# as14120_x31_adc.net
KiCad netlist of a schematic drawn in Altium Designer
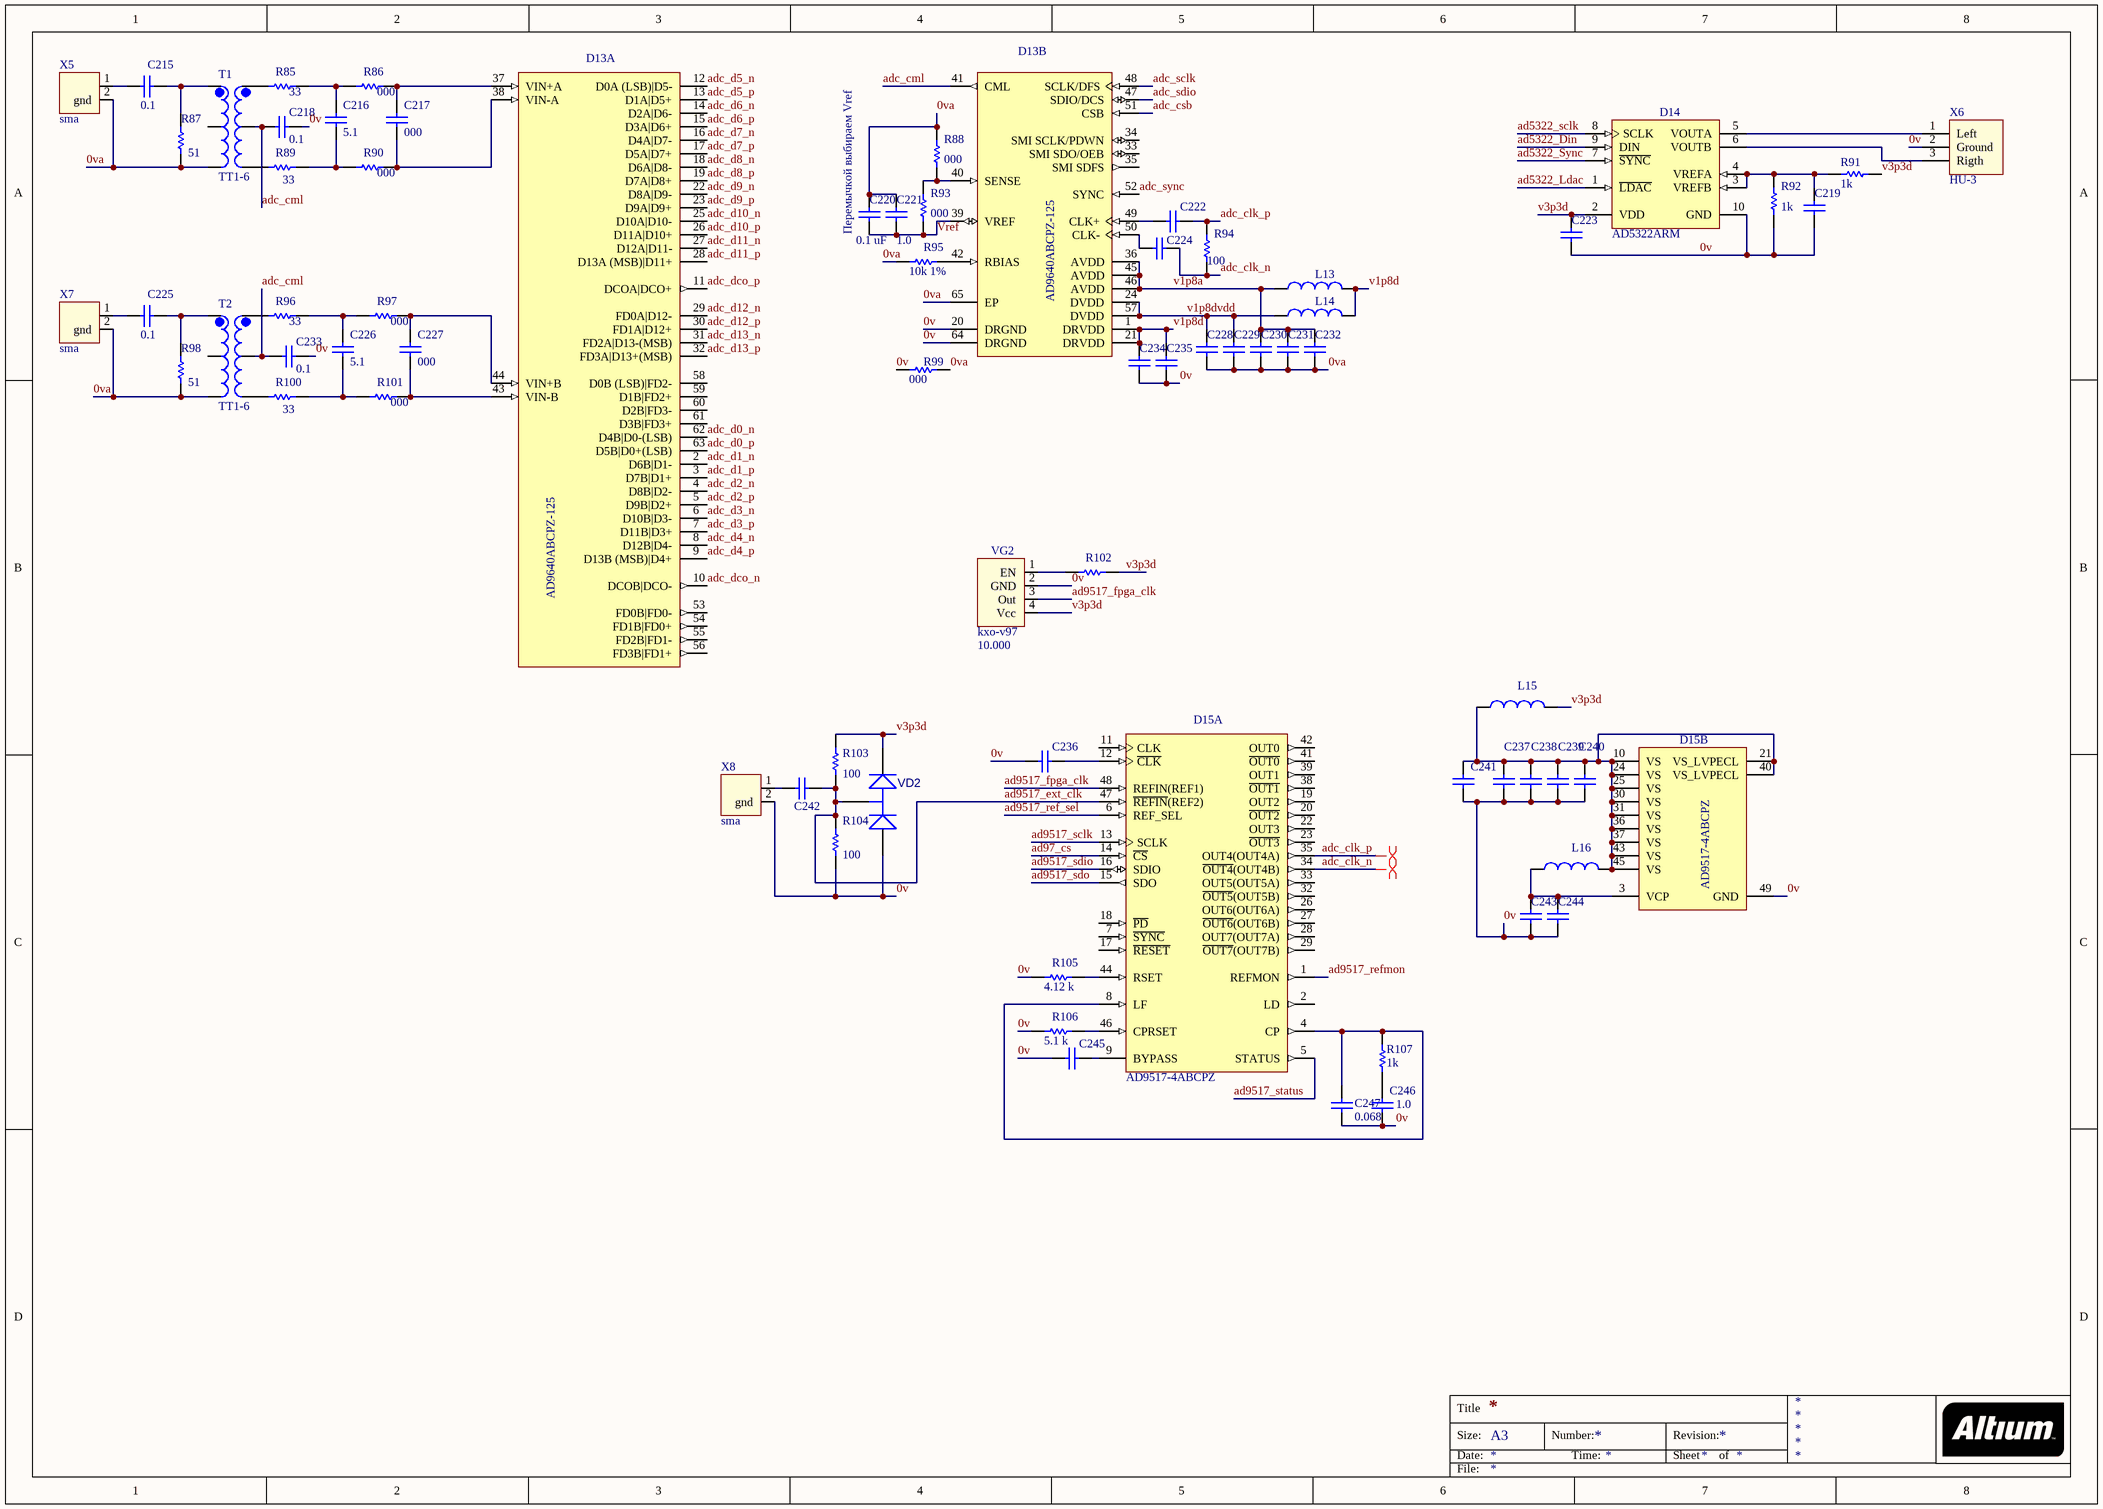
[diagram p0: as14120_x31_adc.SchDoc]

(export (version "E")
  (design (tool "Eeschema 10.0.6"))
  (components
    (comp (ref "C215")
      (value "0.1")
      (footprint "CAPC0402(1005)60_M")
      (description "CAP 1uF 10V ±20% 0402 (1005 Metric) Thickness 0.6mm SMD")
      (fields (field (name "TOLERANCE") "±20%") (field (name "Comment") "CAP 1uF 10V 0402(1005)"))
      (libsource (lib "as14120") (part "CAP_0402"))
    )
    (comp (ref "C216")
      (value "5.1")
      (footprint "CAPC0805(2012)100_N")
      (fields (field (name "Comment") "CAP_0805"))
      (libsource (lib "as14120") (part "CAP_0805"))
    )
    (comp (ref "C217")
      (value "000")
      (footprint "CAPC0805(2012)100_N")
      (fields (field (name "Comment") "CAP_0805"))
      (libsource (lib "as14120") (part "CAP_0805"))
    )
    (comp (ref "C218")
      (value "0.1")
      (footprint "CAPC0402(1005)60_M")
      (description "CAP 1uF 10V ±20% 0402 (1005 Metric) Thickness 0.6mm SMD")
      (fields (field (name "TOLERANCE") "±20%") (field (name "Comment") "CAP 1uF 10V 0402(1005)"))
      (libsource (lib "as14120") (part "CAP_0402"))
    )
    (comp (ref "C219")
      (value "CAP 1uF 10V 0402(1005)")
      (footprint "CAPC0402(1005)60_M")
      (description "CAP 1uF 10V ±20% 0402 (1005 Metric) Thickness 0.6mm SMD")
      (fields (field (name "TOLERANCE") "±20%"))
      (libsource (lib "as14120") (part "CAP_0402"))
    )
    (comp (ref "C220")
      (value "0.1 uF")
      (footprint "CAPC0402(1005)60_M")
      (description "CAP 1uF 10V ±20% 0402 (1005 Metric) Thickness 0.6mm SMD")
      (fields (field (name "TOLERANCE") "±20%") (field (name "Comment") "CAP 1uF 10V 0402(1005)"))
      (libsource (lib "as14120") (part "CAP_0402"))
    )
    (comp (ref "C221")
      (value "1.0")
      (footprint "CAPC0402(1005)60_M")
      (description "CAP 1uF 10V ±20% 0402 (1005 Metric) Thickness 0.6mm SMD")
      (fields (field (name "TOLERANCE") "±20%") (field (name "Comment") "CAP 1uF 10V 0402(1005)"))
      (libsource (lib "as14120") (part "CAP_0402"))
    )
    (comp (ref "C222")
      (value "CAP 1uF 10V 0402(1005)")
      (footprint "CAPC0402(1005)60_M")
      (description "CAP 1uF 10V ±20% 0402 (1005 Metric) Thickness 0.6mm SMD")
      (fields (field (name "TOLERANCE") "±20%"))
      (libsource (lib "as14120") (part "CAP_0402"))
    )
    (comp (ref "C223")
      (value "CAP 1uF 10V 0402(1005)")
      (footprint "CAPC0402(1005)60_M")
      (description "CAP 1uF 10V ±20% 0402 (1005 Metric) Thickness 0.6mm SMD")
      (fields (field (name "TOLERANCE") "±20%"))
      (libsource (lib "as14120") (part "CAP_0402"))
    )
    (comp (ref "C224")
      (value "CAP 1uF 10V 0402(1005)")
      (footprint "CAPC0402(1005)60_M")
      (description "CAP 1uF 10V ±20% 0402 (1005 Metric) Thickness 0.6mm SMD")
      (fields (field (name "TOLERANCE") "±20%"))
      (libsource (lib "as14120") (part "CAP_0402"))
    )
    (comp (ref "C225")
      (value "0.1")
      (footprint "CAPC0402(1005)60_M")
      (description "CAP 1uF 10V ±20% 0402 (1005 Metric) Thickness 0.6mm SMD")
      (fields (field (name "TOLERANCE") "±20%") (field (name "Comment") "CAP 1uF 10V 0402(1005)"))
      (libsource (lib "as14120") (part "CAP_0402"))
    )
    (comp (ref "C226")
      (value "5.1")
      (footprint "CAPC0805(2012)100_N")
      (fields (field (name "Comment") "CAP_0805"))
      (libsource (lib "as14120") (part "CAP_0805"))
    )
    (comp (ref "C227")
      (value "000")
      (footprint "CAPC0805(2012)100_N")
      (fields (field (name "Comment") "CAP_0805"))
      (libsource (lib "as14120") (part "CAP_0805"))
    )
    (comp (ref "C228")
      (value "CAP 1uF 10V 0402(1005)")
      (footprint "CAPC0402(1005)60_M")
      (description "CAP 1uF 10V ±20% 0402 (1005 Metric) Thickness 0.6mm SMD")
      (fields (field (name "TOLERANCE") "±20%"))
      (libsource (lib "as14120") (part "CAP_0402"))
    )
    (comp (ref "C229")
      (value "CAP 1uF 10V 0402(1005)")
      (footprint "CAPC0402(1005)60_M")
      (description "CAP 1uF 10V ±20% 0402 (1005 Metric) Thickness 0.6mm SMD")
      (fields (field (name "TOLERANCE") "±20%"))
      (libsource (lib "as14120") (part "CAP_0402"))
    )
    (comp (ref "C230")
      (value "CAP 1uF 10V 0402(1005)")
      (footprint "CAPC0402(1005)60_M")
      (description "CAP 1uF 10V ±20% 0402 (1005 Metric) Thickness 0.6mm SMD")
      (fields (field (name "TOLERANCE") "±20%"))
      (libsource (lib "as14120") (part "CAP_0402"))
    )
    (comp (ref "C231")
      (value "CAP 1uF 10V 0402(1005)")
      (footprint "CAPC0402(1005)60_M")
      (description "CAP 1uF 10V ±20% 0402 (1005 Metric) Thickness 0.6mm SMD")
      (fields (field (name "TOLERANCE") "±20%"))
      (libsource (lib "as14120") (part "CAP_0402"))
    )
    (comp (ref "C232")
      (value "CAP 1uF 10V 0402(1005)")
      (footprint "CAPC0402(1005)60_M")
      (description "CAP 1uF 10V ±20% 0402 (1005 Metric) Thickness 0.6mm SMD")
      (fields (field (name "TOLERANCE") "±20%"))
      (libsource (lib "as14120") (part "CAP_0402"))
    )
    (comp (ref "C233")
      (value "0.1")
      (footprint "CAPC0402(1005)60_M")
      (description "CAP 1uF 10V ±20% 0402 (1005 Metric) Thickness 0.6mm SMD")
      (fields (field (name "TOLERANCE") "±20%") (field (name "Comment") "CAP 1uF 10V 0402(1005)"))
      (libsource (lib "as14120") (part "CAP_0402"))
    )
    (comp (ref "C234")
      (value "CAP 1uF 10V 0402(1005)")
      (footprint "CAPC0402(1005)60_M")
      (description "CAP 1uF 10V ±20% 0402 (1005 Metric) Thickness 0.6mm SMD")
      (fields (field (name "TOLERANCE") "±20%"))
      (libsource (lib "as14120") (part "CAP_0402"))
    )
    (comp (ref "C235")
      (value "CAP 1uF 10V 0402(1005)")
      (footprint "CAPC0402(1005)60_M")
      (description "CAP 1uF 10V ±20% 0402 (1005 Metric) Thickness 0.6mm SMD")
      (fields (field (name "TOLERANCE") "±20%"))
      (libsource (lib "as14120") (part "CAP_0402"))
    )
    (comp (ref "C236")
      (value "CAP 1uF 10V 0402(1005)")
      (footprint "CAPC0402(1005)60_M")
      (description "CAP 1uF 10V ±20% 0402 (1005 Metric) Thickness 0.6mm SMD")
      (fields (field (name "TOLERANCE") "±20%"))
      (libsource (lib "as14120") (part "CAP_0402"))
    )
    (comp (ref "C237")
      (value "CAP 1uF 10V 0402(1005)")
      (footprint "CAPC0402(1005)60_M")
      (description "CAP 1uF 10V ±20% 0402 (1005 Metric) Thickness 0.6mm SMD")
      (fields (field (name "TOLERANCE") "±20%"))
      (libsource (lib "as14120") (part "CAP_0402"))
    )
    (comp (ref "C238")
      (value "CAP 1uF 10V 0402(1005)")
      (footprint "CAPC0402(1005)60_M")
      (description "CAP 1uF 10V ±20% 0402 (1005 Metric) Thickness 0.6mm SMD")
      (fields (field (name "TOLERANCE") "±20%"))
      (libsource (lib "as14120") (part "CAP_0402"))
    )
    (comp (ref "C239")
      (value "CAP 1uF 10V 0402(1005)")
      (footprint "CAPC0402(1005)60_M")
      (description "CAP 1uF 10V ±20% 0402 (1005 Metric) Thickness 0.6mm SMD")
      (fields (field (name "TOLERANCE") "±20%"))
      (libsource (lib "as14120") (part "CAP_0402"))
    )
    (comp (ref "C240")
      (value "CAP 1uF 10V 0402(1005)")
      (footprint "CAPC0402(1005)60_M")
      (description "CAP 1uF 10V ±20% 0402 (1005 Metric) Thickness 0.6mm SMD")
      (fields (field (name "TOLERANCE") "±20%"))
      (libsource (lib "as14120") (part "CAP_0402"))
    )
    (comp (ref "C241")
      (value "CAP 1uF 10V 0402(1005)")
      (footprint "CAPC0402(1005)60_M")
      (description "CAP 1uF 10V ±20% 0402 (1005 Metric) Thickness 0.6mm SMD")
      (fields (field (name "TOLERANCE") "±20%"))
      (libsource (lib "as14120") (part "CAP_0402"))
    )
    (comp (ref "C242")
      (value "CAP 1uF 10V 0402(1005)")
      (footprint "CAPC0402(1005)60_M")
      (description "CAP 1uF 10V ±20% 0402 (1005 Metric) Thickness 0.6mm SMD")
      (fields (field (name "TOLERANCE") "±20%"))
      (libsource (lib "as14120") (part "CAP_0402"))
    )
    (comp (ref "C243")
      (value "CAP 1uF 10V 0402(1005)")
      (footprint "CAPC0402(1005)60_M")
      (description "CAP 1uF 10V ±20% 0402 (1005 Metric) Thickness 0.6mm SMD")
      (fields (field (name "TOLERANCE") "±20%"))
      (libsource (lib "as14120") (part "CAP_0402"))
    )
    (comp (ref "C244")
      (value "CAP 1uF 10V 0402(1005)")
      (footprint "CAPC0402(1005)60_M")
      (description "CAP 1uF 10V ±20% 0402 (1005 Metric) Thickness 0.6mm SMD")
      (fields (field (name "TOLERANCE") "±20%"))
      (libsource (lib "as14120") (part "CAP_0402"))
    )
    (comp (ref "C245")
      (value "CAP 1uF 10V 0402(1005)")
      (footprint "CAPC0402(1005)60_M")
      (description "CAP 1uF 10V ±20% 0402 (1005 Metric) Thickness 0.6mm SMD")
      (fields (field (name "TOLERANCE") "±20%"))
      (libsource (lib "as14120") (part "CAP_0402"))
    )
    (comp (ref "C246")
      (value "1.0")
      (footprint "CAPC0805(2012)100_N")
      (fields (field (name "Comment") "CAP_0805"))
      (libsource (lib "as14120") (part "CAP_0805"))
    )
    (comp (ref "C247")
      (value "0.068")
      (footprint "CAPC0805(2012)100_N")
      (fields (field (name "Comment") "CAP_0805"))
      (libsource (lib "as14120") (part "CAP_0805"))
    )
    (comp (ref "D13")
      (value "AD9640ABCPZ-125")
      (footprint "CP-64-6_N")
      (fields (field (name "PART NUMBER") "AD9640-125") (field (name "MANUFACTURER") "Analog Devices"))
      (libsource (lib "Analog Devices Data Converters Analog-to-Digital Converters") (part "AD9640ABCPZ-125"))
    )
    (comp (ref "D14")
      (value "AD5322ARM")
      (footprint "RM-10_L")
      (fields (field (name "ADI PART NUMBER") "AD5322") (field (name "MANUFACTURER") "Analog Devices"))
      (libsource (lib "Analog Devices Data Converters Digital-to-Analog Converters") (part "AD5322ARM"))
    )
    (comp (ref "D15")
      (value "AD9517-4ABCPZ")
      (footprint "ADI-CP-48-8_L")
      (libsource (lib "Analog Devices RF IF Timing ICs and Clocks") (part "AD9517-4ABCPZ"))
    )
    (comp (ref "L13")
      (value "BLM21PG300SN1D")
      (footprint "CAPC0805(2012)100_N")
      (libsource (lib "as14120") (part "Ferrite_beat"))
    )
    (comp (ref "L14")
      (value "BLM21PG300SN1D")
      (footprint "CAPC0805(2012)100_N")
      (libsource (lib "as14120") (part "Ferrite_beat"))
    )
    (comp (ref "L15")
      (value "BLM21PG300SN1D")
      (footprint "CAPC0805(2012)100_N")
      (libsource (lib "as14120") (part "Ferrite_beat"))
    )
    (comp (ref "L16")
      (value "BLM21PG300SN1D")
      (footprint "CAPC0805(2012)100_N")
      (libsource (lib "as14120") (part "Ferrite_beat"))
    )
    (comp (ref "R85")
      (value "33")
      (footprint "RESC0805(2012)_L")
      (description "1K 0.125W 1% 0805 (2012 Metric)  SMD")
      (fields (field (name "TOLERANCE") "1 %") (field (name "POWER") "0.125 W"))
      (libsource (lib "as14120") (part "RES_0805"))
    )
    (comp (ref "R86")
      (value "000")
      (footprint "RESC0805(2012)_L")
      (description "1K 0.125W 1% 0805 (2012 Metric)  SMD")
      (fields (field (name "TOLERANCE") "1 %") (field (name "POWER") "0.125 W"))
      (libsource (lib "as14120") (part "RES_0805"))
    )
    (comp (ref "R87")
      (value "51")
      (footprint "RESC0805(2012)_L")
      (description "1K 0.125W 1% 0805 (2012 Metric)  SMD")
      (fields (field (name "TOLERANCE") "1 %") (field (name "POWER") "0.125 W"))
      (libsource (lib "as14120") (part "RES_0805"))
    )
    (comp (ref "R88")
      (value "000")
      (footprint "RESC0603(1608)_L")
      (description "1K 0.1W 5% 0603 (1608 Metric)  SMD")
      (fields (field (name "TOLERANCE") "5 %") (field (name "POWER") "0.1 W"))
      (libsource (lib "as14120") (part "RES_0603"))
    )
    (comp (ref "R89")
      (value "33")
      (footprint "RESC0805(2012)_L")
      (description "1K 0.125W 1% 0805 (2012 Metric)  SMD")
      (fields (field (name "TOLERANCE") "1 %") (field (name "POWER") "0.125 W"))
      (libsource (lib "as14120") (part "RES_0805"))
    )
    (comp (ref "R90")
      (value "000")
      (footprint "RESC0805(2012)_L")
      (description "1K 0.125W 1% 0805 (2012 Metric)  SMD")
      (fields (field (name "TOLERANCE") "1 %") (field (name "POWER") "0.125 W"))
      (libsource (lib "as14120") (part "RES_0805"))
    )
    (comp (ref "R91")
      (value "1k")
      (footprint "RESC0603(1608)_L")
      (description "1K 0.1W 5% 0603 (1608 Metric)  SMD")
      (fields (field (name "TOLERANCE") "5 %") (field (name "POWER") "0.1 W"))
      (libsource (lib "as14120") (part "RES_0603"))
    )
    (comp (ref "R92")
      (value "1k")
      (footprint "RESC0603(1608)_L")
      (description "1K 0.1W 5% 0603 (1608 Metric)  SMD")
      (fields (field (name "TOLERANCE") "5 %") (field (name "POWER") "0.1 W"))
      (libsource (lib "as14120") (part "RES_0603"))
    )
    (comp (ref "R93")
      (value "000")
      (footprint "RESC0603(1608)_L")
      (description "1K 0.1W 5% 0603 (1608 Metric)  SMD")
      (fields (field (name "TOLERANCE") "5 %") (field (name "POWER") "0.1 W"))
      (libsource (lib "as14120") (part "RES_0603"))
    )
    (comp (ref "R94")
      (value "100")
      (footprint "RESC0805(2012)_L")
      (description "1K 0.125W 1% 0805 (2012 Metric)  SMD")
      (fields (field (name "TOLERANCE") "1 %") (field (name "POWER") "0.125 W"))
      (libsource (lib "as14120") (part "RES_0805"))
    )
    (comp (ref "R95")
      (value "10k 1%")
      (footprint "RESC0805(2012)_L")
      (description "1K 0.125W 1% 0805 (2012 Metric)  SMD")
      (fields (field (name "TOLERANCE") "1 %") (field (name "POWER") "0.125 W"))
      (libsource (lib "as14120") (part "RES_0805"))
    )
    (comp (ref "R96")
      (value "33")
      (footprint "RESC0805(2012)_L")
      (description "1K 0.125W 1% 0805 (2012 Metric)  SMD")
      (fields (field (name "TOLERANCE") "1 %") (field (name "POWER") "0.125 W"))
      (libsource (lib "as14120") (part "RES_0805"))
    )
    (comp (ref "R97")
      (value "000")
      (footprint "RESC0805(2012)_L")
      (description "1K 0.125W 1% 0805 (2012 Metric)  SMD")
      (fields (field (name "TOLERANCE") "1 %") (field (name "POWER") "0.125 W"))
      (libsource (lib "as14120") (part "RES_0805"))
    )
    (comp (ref "R98")
      (value "51")
      (footprint "RESC0805(2012)_L")
      (description "1K 0.125W 1% 0805 (2012 Metric)  SMD")
      (fields (field (name "TOLERANCE") "1 %") (field (name "POWER") "0.125 W"))
      (libsource (lib "as14120") (part "RES_0805"))
    )
    (comp (ref "R99")
      (value "000")
      (footprint "RESC0603(1608)_L")
      (description "1K 0.1W 5% 0603 (1608 Metric)  SMD")
      (fields (field (name "TOLERANCE") "5 %") (field (name "POWER") "0.1 W"))
      (libsource (lib "as14120") (part "RES_0603"))
    )
    (comp (ref "R100")
      (value "33")
      (footprint "RESC0805(2012)_L")
      (description "1K 0.125W 1% 0805 (2012 Metric)  SMD")
      (fields (field (name "TOLERANCE") "1 %") (field (name "POWER") "0.125 W"))
      (libsource (lib "as14120") (part "RES_0805"))
    )
    (comp (ref "R101")
      (value "000")
      (footprint "RESC0805(2012)_L")
      (description "1K 0.125W 1% 0805 (2012 Metric)  SMD")
      (fields (field (name "TOLERANCE") "1 %") (field (name "POWER") "0.125 W"))
      (libsource (lib "as14120") (part "RES_0805"))
    )
    (comp (ref "R102")
      (value "1K 5% 0603(1608)")
      (footprint "RESC0603(1608)_L")
      (description "1K 0.1W 5% 0603 (1608 Metric)  SMD")
      (fields (field (name "TOLERANCE") "5 %") (field (name "POWER") "0.1 W"))
      (libsource (lib "as14120") (part "RES_0603"))
    )
    (comp (ref "R103")
      (value "100")
      (footprint "RESC0805(2012)_L")
      (description "1K 0.125W 1% 0805 (2012 Metric)  SMD")
      (fields (field (name "TOLERANCE") "1 %") (field (name "POWER") "0.125 W"))
      (libsource (lib "as14120") (part "RES_0805"))
    )
    (comp (ref "R104")
      (value "100")
      (footprint "RESC0805(2012)_L")
      (description "1K 0.125W 1% 0805 (2012 Metric)  SMD")
      (fields (field (name "TOLERANCE") "1 %") (field (name "POWER") "0.125 W"))
      (libsource (lib "as14120") (part "RES_0805"))
    )
    (comp (ref "R105")
      (value "4.12 k")
      (footprint "RESC0805(2012)_L")
      (description "1K 0.125W 1% 0805 (2012 Metric)  SMD")
      (fields (field (name "TOLERANCE") "1 %") (field (name "POWER") "0.125 W"))
      (libsource (lib "as14120") (part "RES_0805"))
    )
    (comp (ref "R106")
      (value "5.1 k")
      (footprint "RESC0805(2012)_L")
      (description "1K 0.125W 1% 0805 (2012 Metric)  SMD")
      (fields (field (name "TOLERANCE") "1 %") (field (name "POWER") "0.125 W"))
      (libsource (lib "as14120") (part "RES_0805"))
    )
    (comp (ref "R107")
      (value "1k")
      (footprint "RESC0805(2012)_L")
      (description "1K 0.125W 1% 0805 (2012 Metric)  SMD")
      (fields (field (name "TOLERANCE") "1 %") (field (name "POWER") "0.125 W"))
      (libsource (lib "as14120") (part "RES_0805"))
    )
    (comp (ref "T1") (value "TT1-6") (footprint "TT!-6-KK81") (libsource (lib "as14120") (part "TT1-6-KK81")))
    (comp (ref "T2") (value "TT1-6") (footprint "TT!-6-KK81") (libsource (lib "as14120") (part "TT1-6-KK81")))
    (comp (ref "VD2")
      (value "BAV99")
      (footprint "SO-G3/X.9")
      (description "SOT23 Silicon Planar High-Speed Switching Series Diode Pair")
      (libsource (lib "alexsb") (part "BAV99"))
    )
    (comp (ref "VG2")
      (value "kxo-v97")
      (footprint "kxo-v97")
      (fields (field (name "ALTIUM_VALUE") "10.000"))
      (libsource (lib "as14120") (part "kxo-v97"))
    )
    (comp (ref "X5") (value "sma") (footprint "sma") (libsource (lib "as14120") (part "sma")))
    (comp (ref "X6") (value "HU-3") (footprint "HU-3") (libsource (lib "as14120") (part "HU-3")))
    (comp (ref "X7") (value "sma") (footprint "sma") (libsource (lib "as14120") (part "sma")))
    (comp (ref "X8") (value "sma") (footprint "sma") (libsource (lib "as14120") (part "sma")))
  )
  (nets
    (net (code "1") (name "/0v") (class "Default")
      (node (ref "C218") (pin "2") (pinfunction "2_2") (pintype "passive"))
      (node (ref "C219") (pin "1") (pinfunction "1_1") (pintype "passive"))
      (node (ref "C223") (pin "1") (pinfunction "1_1") (pintype "passive"))
      (node (ref "C233") (pin "2") (pinfunction "2_2") (pintype "passive"))
      (node (ref "C234") (pin "1") (pinfunction "1_1") (pintype "passive"))
      (node (ref "C235") (pin "1") (pinfunction "1_1") (pintype "passive"))
      (node (ref "C236") (pin "1") (pinfunction "1_1") (pintype "passive"))
      (node (ref "C237") (pin "1") (pinfunction "1_1") (pintype "passive"))
      (node (ref "C238") (pin "1") (pinfunction "1_1") (pintype "passive"))
      (node (ref "C239") (pin "1") (pinfunction "1_1") (pintype "passive"))
      (node (ref "C240") (pin "1") (pinfunction "1_1") (pintype "passive"))
      (node (ref "C241") (pin "1") (pinfunction "1_1") (pintype "passive"))
      (node (ref "C243") (pin "1") (pinfunction "1_1") (pintype "passive"))
      (node (ref "C244") (pin "1") (pinfunction "1_1") (pintype "passive"))
      (node (ref "C245") (pin "1") (pinfunction "1_1") (pintype "passive"))
      (node (ref "C246") (pin "1") (pinfunction "1_1") (pintype "passive"))
      (node (ref "C247") (pin "1") (pinfunction "1_1") (pintype "passive"))
      (node (ref "D13") (pin "20") (pinfunction "DRGND_20") (pintype "power_in"))
      (node (ref "D13") (pin "64") (pinfunction "DRGND_64") (pintype "power_in"))
      (node (ref "D14") (pin "10") (pinfunction "GND_10") (pintype "power_in"))
      (node (ref "D15") (pin "49") (pinfunction "GND_49") (pintype "power_in"))
      (node (ref "R104") (pin "1") (pinfunction "1_1") (pintype "passive"))
      (node (ref "R105") (pin "2") (pinfunction "2_2") (pintype "passive"))
      (node (ref "R106") (pin "2") (pinfunction "2_2") (pintype "passive"))
      (node (ref "R92") (pin "2") (pinfunction "2_2") (pintype "passive"))
      (node (ref "R99") (pin "1") (pinfunction "1_1") (pintype "passive"))
      (node (ref "VD2") (pin "3") (pinfunction "A_3") (pintype "passive"))
      (node (ref "VG2") (pin "2") (pinfunction "GND_2") (pintype "passive"))
      (node (ref "X6") (pin "2") (pinfunction "Ground_2") (pintype "passive"))
      (node (ref "X8") (pin "2") (pinfunction "gnd_2") (pintype "passive"))
    )
    (net (code "2") (name "/0va") (class "Default")
      (node (ref "C220") (pin "2") (pinfunction "2_2") (pintype "passive"))
      (node (ref "C221") (pin "2") (pinfunction "2_2") (pintype "passive"))
      (node (ref "C228") (pin "1") (pinfunction "1_1") (pintype "passive"))
      (node (ref "C229") (pin "1") (pinfunction "1_1") (pintype "passive"))
      (node (ref "C230") (pin "1") (pinfunction "1_1") (pintype "passive"))
      (node (ref "C231") (pin "1") (pinfunction "1_1") (pintype "passive"))
      (node (ref "C232") (pin "1") (pinfunction "1_1") (pintype "passive"))
      (node (ref "D13") (pin "65") (pinfunction "EP_65") (pintype "power_in"))
      (node (ref "R87") (pin "1") (pinfunction "1_1") (pintype "passive"))
      (node (ref "R88") (pin "1") (pinfunction "1_1") (pintype "passive"))
      (node (ref "R95") (pin "2") (pinfunction "2_2") (pintype "passive"))
      (node (ref "R98") (pin "1") (pinfunction "1_1") (pintype "passive"))
      (node (ref "R99") (pin "2") (pinfunction "2_2") (pintype "passive"))
      (node (ref "T1") (pin "6") (pinfunction "6_6") (pintype "passive"))
      (node (ref "T2") (pin "6") (pinfunction "6_6") (pintype "passive"))
      (node (ref "X5") (pin "2") (pinfunction "gnd_2") (pintype "passive"))
      (node (ref "X7") (pin "2") (pinfunction "gnd_2") (pintype "passive"))
    )
    (net (code "3") (name "/Vref") (class "Default")
      (node (ref "C220") (pin "1") (pinfunction "1_1") (pintype "passive"))
      (node (ref "C221") (pin "1") (pinfunction "1_1") (pintype "passive"))
      (node (ref "D13") (pin "39") (pinfunction "VREF_39") (pintype "bidirectional"))
      (node (ref "R93") (pin "2") (pinfunction "2_2") (pintype "passive"))
    )
    (net (code "4") (name "/ad97_cs") (class "Default")
      (node (ref "D15") (pin "14") (pinfunction "~{CS}_14") (pintype "input"))
    )
    (net (code "5") (name "/ad5322_Din") (class "Default")
      (node (ref "D14") (pin "9") (pinfunction "DIN_9") (pintype "input"))
    )
    (net (code "6") (name "/ad5322_Ldac") (class "Default")
      (node (ref "D14") (pin "1") (pinfunction "~{LDAC}_1") (pintype "input"))
    )
    (net (code "7") (name "/ad5322_Sync") (class "Default")
      (node (ref "D14") (pin "7") (pinfunction "~{SYNC}_7") (pintype "input"))
    )
    (net (code "8") (name "/ad5322_sclk") (class "Default")
      (node (ref "D14") (pin "8") (pinfunction "SCLK_8") (pintype "input"))
    )
    (net (code "9") (name "/ad9517_ext_clk") (class "Default")
      (node (ref "C242") (pin "2") (pinfunction "2_2") (pintype "passive"))
      (node (ref "D15") (pin "47") (pinfunction "~{REFIN}(REF2)_47") (pintype "input"))
      (node (ref "R103") (pin "1") (pinfunction "1_1") (pintype "passive"))
      (node (ref "R104") (pin "2") (pinfunction "2_2") (pintype "passive"))
      (node (ref "VD2") (pin "1") (pinfunction "C_1") (pintype "passive"))
    )
    (net (code "10") (name "/ad9517_fpga_clk") (class "Default")
      (node (ref "D15") (pin "48") (pinfunction "REFIN(REF1)_48") (pintype "input"))
      (node (ref "VG2") (pin "3") (pinfunction "Out_3") (pintype "passive"))
    )
    (net (code "11") (name "/ad9517_ref_sel") (class "Default")
      (node (ref "D15") (pin "6") (pinfunction "REF_SEL_6") (pintype "input"))
    )
    (net (code "12") (name "/ad9517_refmon") (class "Default")
      (node (ref "D15") (pin "1") (pinfunction "REFMON_1") (pintype "output"))
    )
    (net (code "13") (name "/ad9517_sclk") (class "Default")
      (node (ref "D15") (pin "13") (pinfunction "SCLK_13") (pintype "input"))
    )
    (net (code "14") (name "/ad9517_sdio") (class "Default")
      (node (ref "D15") (pin "16") (pinfunction "SDIO_16") (pintype "bidirectional"))
    )
    (net (code "15") (name "/ad9517_sdo") (class "Default")
      (node (ref "D15") (pin "15") (pinfunction "SDO_15") (pintype "output"))
    )
    (net (code "16") (name "/ad9517_status") (class "Default")
      (node (ref "D15") (pin "5") (pinfunction "STATUS_5") (pintype "output"))
    )
    (net (code "17") (name "/adc_clk_n") (class "Default")
      (node (ref "C224") (pin "1") (pinfunction "1_1") (pintype "passive"))
      (node (ref "D15") (pin "34") (pinfunction "~{OUT4}(OUT4B)_34") (pintype "output"))
      (node (ref "R94") (pin "1") (pinfunction "1_1") (pintype "passive"))
    )
    (net (code "18") (name "/adc_clk_p") (class "Default")
      (node (ref "C222") (pin "1") (pinfunction "1_1") (pintype "passive"))
      (node (ref "D15") (pin "35") (pinfunction "OUT4(OUT4A)_35") (pintype "output"))
      (node (ref "R94") (pin "2") (pinfunction "2_2") (pintype "passive"))
    )
    (net (code "19") (name "/adc_cml") (class "Default")
      (node (ref "C218") (pin "1") (pinfunction "1_1") (pintype "passive"))
      (node (ref "C233") (pin "1") (pinfunction "1_1") (pintype "passive"))
      (node (ref "D13") (pin "41") (pinfunction "CML_41") (pintype "output"))
      (node (ref "T1") (pin "2") (pinfunction "2_2") (pintype "passive"))
      (node (ref "T2") (pin "2") (pinfunction "2_2") (pintype "passive"))
    )
    (net (code "20") (name "/adc_csb") (class "Default")
      (node (ref "D13") (pin "51") (pinfunction "CSB_51") (pintype "input"))
    )
    (net (code "21") (name "/adc_d0_n") (class "Default")
      (node (ref "D13") (pin "62") (pinfunction "D4BD0-(LSB)_62") (pintype "tri_state"))
    )
    (net (code "22") (name "/adc_d0_p") (class "Default")
      (node (ref "D13") (pin "63") (pinfunction "D5BD0+(LSB)_63") (pintype "tri_state"))
    )
    (net (code "23") (name "/adc_d1_n") (class "Default")
      (node (ref "D13") (pin "2") (pinfunction "D6BD1-_2") (pintype "tri_state"))
    )
    (net (code "24") (name "/adc_d1_p") (class "Default")
      (node (ref "D13") (pin "3") (pinfunction "D7BD1+_3") (pintype "tri_state"))
    )
    (net (code "25") (name "/adc_d2_n") (class "Default")
      (node (ref "D13") (pin "4") (pinfunction "D8BD2-_4") (pintype "tri_state"))
    )
    (net (code "26") (name "/adc_d2_p") (class "Default")
      (node (ref "D13") (pin "5") (pinfunction "D9BD2+_5") (pintype "tri_state"))
    )
    (net (code "27") (name "/adc_d3_n") (class "Default")
      (node (ref "D13") (pin "6") (pinfunction "D10BD3-_6") (pintype "tri_state"))
    )
    (net (code "28") (name "/adc_d3_p") (class "Default")
      (node (ref "D13") (pin "7") (pinfunction "D11BD3+_7") (pintype "tri_state"))
    )
    (net (code "29") (name "/adc_d4_n") (class "Default")
      (node (ref "D13") (pin "8") (pinfunction "D12BD4-_8") (pintype "tri_state"))
    )
    (net (code "30") (name "/adc_d4_p") (class "Default")
      (node (ref "D13") (pin "9") (pinfunction "D13B_(MSB)D4+_9") (pintype "tri_state"))
    )
    (net (code "31") (name "/adc_d5_n") (class "Default")
      (node (ref "D13") (pin "12") (pinfunction "D0A_(LSB)D5-_12") (pintype "tri_state"))
    )
    (net (code "32") (name "/adc_d5_p") (class "Default")
      (node (ref "D13") (pin "13") (pinfunction "D1AD5+_13") (pintype "tri_state"))
    )
    (net (code "33") (name "/adc_d6_n") (class "Default")
      (node (ref "D13") (pin "14") (pinfunction "D2AD6-_14") (pintype "tri_state"))
    )
    (net (code "34") (name "/adc_d6_p") (class "Default")
      (node (ref "D13") (pin "15") (pinfunction "D3AD6+_15") (pintype "tri_state"))
    )
    (net (code "35") (name "/adc_d7_n") (class "Default")
      (node (ref "D13") (pin "16") (pinfunction "D4AD7-_16") (pintype "tri_state"))
    )
    (net (code "36") (name "/adc_d7_p") (class "Default")
      (node (ref "D13") (pin "17") (pinfunction "D5AD7+_17") (pintype "tri_state"))
    )
    (net (code "37") (name "/adc_d8_n") (class "Default")
      (node (ref "D13") (pin "18") (pinfunction "D6AD8-_18") (pintype "tri_state"))
    )
    (net (code "38") (name "/adc_d8_p") (class "Default")
      (node (ref "D13") (pin "19") (pinfunction "D7AD8+_19") (pintype "tri_state"))
    )
    (net (code "39") (name "/adc_d9_n") (class "Default")
      (node (ref "D13") (pin "22") (pinfunction "D8AD9-_22") (pintype "tri_state"))
    )
    (net (code "40") (name "/adc_d9_p") (class "Default")
      (node (ref "D13") (pin "23") (pinfunction "D9AD9+_23") (pintype "tri_state"))
    )
    (net (code "41") (name "/adc_d10_n") (class "Default")
      (node (ref "D13") (pin "25") (pinfunction "D10AD10-_25") (pintype "tri_state"))
    )
    (net (code "42") (name "/adc_d10_p") (class "Default")
      (node (ref "D13") (pin "26") (pinfunction "D11AD10+_26") (pintype "tri_state"))
    )
    (net (code "43") (name "/adc_d11_n") (class "Default")
      (node (ref "D13") (pin "27") (pinfunction "D12AD11-_27") (pintype "tri_state"))
    )
    (net (code "44") (name "/adc_d11_p") (class "Default")
      (node (ref "D13") (pin "28") (pinfunction "D13A_(MSB)D11+_28") (pintype "tri_state"))
    )
    (net (code "45") (name "/adc_d12_n") (class "Default")
      (node (ref "D13") (pin "29") (pinfunction "FD0AD12-_29") (pintype "tri_state"))
    )
    (net (code "46") (name "/adc_d12_p") (class "Default")
      (node (ref "D13") (pin "30") (pinfunction "FD1AD12+_30") (pintype "tri_state"))
    )
    (net (code "47") (name "/adc_d13_n") (class "Default")
      (node (ref "D13") (pin "31") (pinfunction "FD2AD13-(MSB)_31") (pintype "tri_state"))
    )
    (net (code "48") (name "/adc_d13_p") (class "Default")
      (node (ref "D13") (pin "32") (pinfunction "FD3AD13+(MSB)_32") (pintype "tri_state"))
    )
    (net (code "49") (name "/adc_dco_n") (class "Default")
      (node (ref "D13") (pin "10") (pinfunction "DCOBDCO-_10") (pintype "output"))
    )
    (net (code "50") (name "/adc_dco_p") (class "Default")
      (node (ref "D13") (pin "11") (pinfunction "DCOADCO+_11") (pintype "output"))
    )
    (net (code "51") (name "/adc_sclk") (class "Default")
      (node (ref "D13") (pin "48") (pinfunction "SCLK/DFS_48") (pintype "input"))
    )
    (net (code "52") (name "/adc_sdio") (class "Default")
      (node (ref "D13") (pin "47") (pinfunction "SDIO/DCS_47") (pintype "bidirectional"))
    )
    (net (code "53") (name "/adc_sync") (class "Default")
      (node (ref "D13") (pin "52") (pinfunction "SYNC_52") (pintype "input"))
    )
    (net (code "54") (name "/v1p8a") (class "Default")
      (node (ref "C230") (pin "2") (pinfunction "2_2") (pintype "passive"))
      (node (ref "C231") (pin "2") (pinfunction "2_2") (pintype "passive"))
      (node (ref "C232") (pin "2") (pinfunction "2_2") (pintype "passive"))
      (node (ref "D13") (pin "36") (pinfunction "AVDD_36") (pintype "power_in"))
      (node (ref "D13") (pin "45") (pinfunction "AVDD_45") (pintype "power_in"))
      (node (ref "D13") (pin "46") (pinfunction "AVDD_46") (pintype "power_in"))
      (node (ref "L13") (pin "1") (pinfunction "1_1") (pintype "passive"))
    )
    (net (code "55") (name "/v1p8d") (class "Default")
      (node (ref "C234") (pin "2") (pinfunction "2_2") (pintype "passive"))
      (node (ref "C235") (pin "2") (pinfunction "2_2") (pintype "passive"))
      (node (ref "D13") (pin "1") (pinfunction "DRVDD_1") (pintype "power_in"))
      (node (ref "D13") (pin "21") (pinfunction "DRVDD_21") (pintype "power_in"))
      (node (ref "L13") (pin "2") (pinfunction "2_2") (pintype "passive"))
      (node (ref "L14") (pin "2") (pinfunction "2_2") (pintype "passive"))
    )
    (net (code "56") (name "/v1p8dvdd") (class "Default")
      (node (ref "C228") (pin "2") (pinfunction "2_2") (pintype "passive"))
      (node (ref "C229") (pin "2") (pinfunction "2_2") (pintype "passive"))
      (node (ref "D13") (pin "24") (pinfunction "DVDD_24") (pintype "power_in"))
      (node (ref "D13") (pin "57") (pinfunction "DVDD_57") (pintype "power_in"))
      (node (ref "L14") (pin "1") (pinfunction "1_1") (pintype "passive"))
    )
    (net (code "57") (name "/v3p3d") (class "Default")
      (node (ref "C223") (pin "2") (pinfunction "2_2") (pintype "passive"))
      (node (ref "D14") (pin "2") (pinfunction "VDD_2") (pintype "power_in"))
      (node (ref "L15") (pin "2") (pinfunction "2_2") (pintype "passive"))
      (node (ref "R102") (pin "1") (pinfunction "1_1") (pintype "passive"))
      (node (ref "R103") (pin "2") (pinfunction "2_2") (pintype "passive"))
      (node (ref "R91") (pin "2") (pinfunction "2_2") (pintype "passive"))
      (node (ref "VD2") (pin "2") (pinfunction "K_2") (pintype "passive"))
      (node (ref "VG2") (pin "4") (pinfunction "Vcc_4") (pintype "passive"))
    )
    (net (code "58") (name "Net-(C215-Pad1)") (class "Default")
      (node (ref "C215") (pin "1") (pinfunction "1_1") (pintype "passive"))
      (node (ref "X5") (pin "1") (pintype "passive"))
    )
    (net (code "59") (name "Net-(C215-Pad2)") (class "Default")
      (node (ref "C215") (pin "2") (pinfunction "2_2") (pintype "passive"))
      (node (ref "R87") (pin "2") (pinfunction "2_2") (pintype "passive"))
      (node (ref "T1") (pin "4") (pinfunction "4_4") (pintype "passive"))
    )
    (net (code "60") (name "Net-(C216-Pad1)") (class "Default")
      (node (ref "C216") (pin "1") (pinfunction "1_1") (pintype "passive"))
      (node (ref "R89") (pin "1") (pinfunction "1_1") (pintype "passive"))
      (node (ref "R90") (pin "2") (pinfunction "2_2") (pintype "passive"))
    )
    (net (code "61") (name "Net-(C216-Pad2)") (class "Default")
      (node (ref "C216") (pin "2") (pinfunction "2_2") (pintype "passive"))
      (node (ref "R85") (pin "1") (pinfunction "1_1") (pintype "passive"))
      (node (ref "R86") (pin "2") (pinfunction "2_2") (pintype "passive"))
    )
    (net (code "62") (name "Net-(C225-Pad1)") (class "Default")
      (node (ref "C225") (pin "1") (pinfunction "1_1") (pintype "passive"))
      (node (ref "X7") (pin "1") (pintype "passive"))
    )
    (net (code "63") (name "Net-(C225-Pad2)") (class "Default")
      (node (ref "C225") (pin "2") (pinfunction "2_2") (pintype "passive"))
      (node (ref "R98") (pin "2") (pinfunction "2_2") (pintype "passive"))
      (node (ref "T2") (pin "4") (pinfunction "4_4") (pintype "passive"))
    )
    (net (code "64") (name "Net-(C226-Pad1)") (class "Default")
      (node (ref "C226") (pin "1") (pinfunction "1_1") (pintype "passive"))
      (node (ref "R100") (pin "1") (pinfunction "1_1") (pintype "passive"))
      (node (ref "R101") (pin "2") (pinfunction "2_2") (pintype "passive"))
    )
    (net (code "65") (name "Net-(C226-Pad2)") (class "Default")
      (node (ref "C226") (pin "2") (pinfunction "2_2") (pintype "passive"))
      (node (ref "R96") (pin "1") (pinfunction "1_1") (pintype "passive"))
      (node (ref "R97") (pin "2") (pinfunction "2_2") (pintype "passive"))
    )
    (net (code "66") (name "Net-(C237-Pad2)") (class "Default")
      (node (ref "C237") (pin "2") (pinfunction "2_2") (pintype "passive"))
      (node (ref "C238") (pin "2") (pinfunction "2_2") (pintype "passive"))
      (node (ref "C239") (pin "2") (pinfunction "2_2") (pintype "passive"))
      (node (ref "C240") (pin "2") (pinfunction "2_2") (pintype "passive"))
      (node (ref "C241") (pin "2") (pinfunction "2_2") (pintype "passive"))
      (node (ref "D15") (pin "10") (pinfunction "VS_10") (pintype "power_in"))
      (node (ref "D15") (pin "21") (pinfunction "VS_LVPECL_21") (pintype "power_in"))
      (node (ref "D15") (pin "24") (pinfunction "VS_24") (pintype "power_in"))
      (node (ref "D15") (pin "25") (pinfunction "VS_25") (pintype "power_in"))
      (node (ref "D15") (pin "30") (pinfunction "VS_30") (pintype "power_in"))
      (node (ref "D15") (pin "31") (pinfunction "VS_31") (pintype "power_in"))
      (node (ref "D15") (pin "36") (pinfunction "VS_36") (pintype "power_in"))
      (node (ref "D15") (pin "37") (pinfunction "VS_37") (pintype "power_in"))
      (node (ref "D15") (pin "40") (pinfunction "VS_LVPECL_40") (pintype "power_in"))
      (node (ref "D15") (pin "43") (pinfunction "VS_43") (pintype "power_in"))
      (node (ref "D15") (pin "45") (pinfunction "VS_45") (pintype "power_in"))
      (node (ref "L15") (pin "1") (pinfunction "1_1") (pintype "passive"))
      (node (ref "L16") (pin "2") (pinfunction "2_2") (pintype "passive"))
    )
    (net (code "67") (name "Net-(C242-Pad1)") (class "Default")
      (node (ref "C242") (pin "1") (pinfunction "1_1") (pintype "passive"))
      (node (ref "X8") (pin "1") (pintype "passive"))
    )
    (net (code "68") (name "Net-(C246-Pad2)") (class "Default")
      (node (ref "C246") (pin "2") (pinfunction "2_2") (pintype "passive"))
      (node (ref "R107") (pin "2") (pinfunction "2_2") (pintype "passive"))
    )
    (net (code "69") (name "Net-(D13A-VIN+A)") (class "Default")
      (node (ref "C217") (pin "2") (pinfunction "2_2") (pintype "passive"))
      (node (ref "D13") (pin "37") (pinfunction "VIN+A_37") (pintype "input"))
      (node (ref "R86") (pin "1") (pinfunction "1_1") (pintype "passive"))
    )
    (net (code "70") (name "Net-(D13A-VIN+B)") (class "Default")
      (node (ref "C227") (pin "2") (pinfunction "2_2") (pintype "passive"))
      (node (ref "D13") (pin "44") (pinfunction "VIN+B_44") (pintype "input"))
      (node (ref "R97") (pin "1") (pinfunction "1_1") (pintype "passive"))
    )
    (net (code "71") (name "Net-(D13A-VIN-A)") (class "Default")
      (node (ref "C217") (pin "1") (pinfunction "1_1") (pintype "passive"))
      (node (ref "D13") (pin "38") (pinfunction "VIN-A_38") (pintype "input"))
      (node (ref "R90") (pin "1") (pinfunction "1_1") (pintype "passive"))
    )
    (net (code "72") (name "Net-(D13A-VIN-B)") (class "Default")
      (node (ref "C227") (pin "1") (pinfunction "1_1") (pintype "passive"))
      (node (ref "D13") (pin "43") (pinfunction "VIN-B_43") (pintype "input"))
      (node (ref "R101") (pin "1") (pinfunction "1_1") (pintype "passive"))
    )
    (net (code "73") (name "Net-(D13B-CLK+)") (class "Default")
      (node (ref "C222") (pin "2") (pinfunction "2_2") (pintype "passive"))
      (node (ref "D13") (pin "49") (pinfunction "CLK+_49") (pintype "input"))
    )
    (net (code "74") (name "Net-(D13B-CLK-)") (class "Default")
      (node (ref "C224") (pin "2") (pinfunction "2_2") (pintype "passive"))
      (node (ref "D13") (pin "50") (pinfunction "CLK-_50") (pintype "input"))
    )
    (net (code "75") (name "Net-(D13B-RBIAS)") (class "Default")
      (node (ref "D13") (pin "42") (pinfunction "RBIAS_42") (pintype "input"))
      (node (ref "R95") (pin "1") (pinfunction "1_1") (pintype "passive"))
    )
    (net (code "76") (name "Net-(D13B-SENSE)") (class "Default")
      (node (ref "D13") (pin "40") (pinfunction "SENSE_40") (pintype "input"))
      (node (ref "R88") (pin "2") (pinfunction "2_2") (pintype "passive"))
      (node (ref "R93") (pin "1") (pinfunction "1_1") (pintype "passive"))
    )
    (net (code "77") (name "Net-(D14-VOUTA)") (class "Default")
      (node (ref "D14") (pin "5") (pinfunction "VOUTA_5") (pintype "tri_state"))
      (node (ref "X6") (pin "1") (pinfunction "Left_1") (pintype "passive"))
    )
    (net (code "78") (name "Net-(D14-VOUTB)") (class "Default")
      (node (ref "D14") (pin "6") (pinfunction "VOUTB_6") (pintype "tri_state"))
      (node (ref "X6") (pin "3") (pinfunction "Rigth_3") (pintype "passive"))
    )
    (net (code "79") (name "Net-(D14-VREFA)") (class "Default")
      (node (ref "C219") (pin "2") (pinfunction "2_2") (pintype "passive"))
      (node (ref "D14") (pin "3") (pinfunction "VREFB_3") (pintype "input"))
      (node (ref "D14") (pin "4") (pinfunction "VREFA_4") (pintype "input"))
      (node (ref "R91") (pin "1") (pinfunction "1_1") (pintype "passive"))
      (node (ref "R92") (pin "1") (pinfunction "1_1") (pintype "passive"))
    )
    (net (code "80") (name "Net-(D15A-BYPASS)") (class "Default")
      (node (ref "C245") (pin "2") (pinfunction "2_2") (pintype "passive"))
      (node (ref "D15") (pin "9") (pinfunction "BYPASS_9") (pintype "passive"))
    )
    (net (code "81") (name "Net-(D15A-CP)") (class "Default")
      (node (ref "C247") (pin "2") (pinfunction "2_2") (pintype "passive"))
      (node (ref "D15") (pin "4") (pinfunction "CP_4") (pintype "output"))
      (node (ref "D15") (pin "8") (pinfunction "LF_8") (pintype "input"))
      (node (ref "R107") (pin "1") (pinfunction "1_1") (pintype "passive"))
    )
    (net (code "82") (name "Net-(D15A-CPRSET)") (class "Default")
      (node (ref "D15") (pin "46") (pinfunction "CPRSET_46") (pintype "input"))
      (node (ref "R106") (pin "1") (pinfunction "1_1") (pintype "passive"))
    )
    (net (code "83") (name "Net-(D15A-RSET)") (class "Default")
      (node (ref "D15") (pin "44") (pinfunction "RSET_44") (pintype "input"))
      (node (ref "R105") (pin "1") (pinfunction "1_1") (pintype "passive"))
    )
    (net (code "84") (name "Net-(D15A-~{CLK})") (class "Default")
      (node (ref "C236") (pin "2") (pinfunction "2_2") (pintype "passive"))
      (node (ref "D15") (pin "12") (pinfunction "~{CLK}_12") (pintype "input"))
    )
    (net (code "85") (name "Net-(D15B-VCP)") (class "Default")
      (node (ref "C243") (pin "2") (pinfunction "2_2") (pintype "passive"))
      (node (ref "C244") (pin "2") (pinfunction "2_2") (pintype "passive"))
      (node (ref "D15") (pin "3") (pinfunction "VCP_3") (pintype "power_in"))
      (node (ref "L16") (pin "1") (pinfunction "1_1") (pintype "passive"))
    )
    (net (code "86") (name "Net-(R85-Pad2)") (class "Default")
      (node (ref "R85") (pin "2") (pinfunction "2_2") (pintype "passive"))
      (node (ref "T1") (pin "3") (pinfunction "3_3") (pintype "passive"))
    )
    (net (code "87") (name "Net-(R89-Pad2)") (class "Default")
      (node (ref "R89") (pin "2") (pinfunction "2_2") (pintype "passive"))
      (node (ref "T1") (pin "1") (pinfunction "1_1") (pintype "passive"))
    )
    (net (code "88") (name "Net-(R96-Pad2)") (class "Default")
      (node (ref "R96") (pin "2") (pinfunction "2_2") (pintype "passive"))
      (node (ref "T2") (pin "3") (pinfunction "3_3") (pintype "passive"))
    )
    (net (code "89") (name "Net-(R100-Pad2)") (class "Default")
      (node (ref "R100") (pin "2") (pinfunction "2_2") (pintype "passive"))
      (node (ref "T2") (pin "1") (pinfunction "1_1") (pintype "passive"))
    )
    (net (code "90") (name "Net-(VG2-EN)") (class "Default")
      (node (ref "R102") (pin "2") (pinfunction "2_2") (pintype "passive"))
      (node (ref "VG2") (pin "1") (pinfunction "EN_1") (pintype "passive"))
    )
    (net (code "91") (name "unconnected-(D13A-D0B_(LSB)FD2--Pad58)") (class "Default")
      (node (ref "D13") (pin "58") (pinfunction "D0B_(LSB)FD2-_58") (pintype "tri_state"))
    )
    (net (code "92") (name "unconnected-(D13A-D1BFD2+-Pad59)") (class "Default")
      (node (ref "D13") (pin "59") (pinfunction "D1BFD2+_59") (pintype "tri_state"))
    )
    (net (code "93") (name "unconnected-(D13A-D2BFD3--Pad60)") (class "Default")
      (node (ref "D13") (pin "60") (pinfunction "D2BFD3-_60") (pintype "tri_state"))
    )
    (net (code "94") (name "unconnected-(D13A-D3BFD3+-Pad61)") (class "Default")
      (node (ref "D13") (pin "61") (pinfunction "D3BFD3+_61") (pintype "tri_state"))
    )
    (net (code "95") (name "unconnected-(D13A-FD0BFD0--Pad53)") (class "Default")
      (node (ref "D13") (pin "53") (pinfunction "FD0BFD0-_53") (pintype "output"))
    )
    (net (code "96") (name "unconnected-(D13A-FD1BFD0+-Pad54)") (class "Default")
      (node (ref "D13") (pin "54") (pinfunction "FD1BFD0+_54") (pintype "output"))
    )
    (net (code "97") (name "unconnected-(D13A-FD2BFD1--Pad55)") (class "Default")
      (node (ref "D13") (pin "55") (pinfunction "FD2BFD1-_55") (pintype "output"))
    )
    (net (code "98") (name "unconnected-(D13A-FD3BFD1+-Pad56)") (class "Default")
      (node (ref "D13") (pin "56") (pinfunction "FD3BFD1+_56") (pintype "output"))
    )
    (net (code "99") (name "unconnected-(D13B-SMI_SCLK{slash}PDWN-Pad34)") (class "Default")
      (node (ref "D13") (pin "34") (pinfunction "SMI_SCLK/PDWN_34") (pintype "bidirectional"))
    )
    (net (code "100") (name "unconnected-(D13B-SMI_SDFS-Pad35)") (class "Default")
      (node (ref "D13") (pin "35") (pinfunction "SMI_SDFS_35") (pintype "output"))
    )
    (net (code "101") (name "unconnected-(D13B-SMI_SDO{slash}OEB-Pad33)") (class "Default")
      (node (ref "D13") (pin "33") (pinfunction "SMI_SDO/OEB_33") (pintype "bidirectional"))
    )
    (net (code "102") (name "unconnected-(D15A-CLK-Pad11)") (class "Default")
      (node (ref "D15") (pin "11") (pinfunction "CLK_11") (pintype "input"))
    )
    (net (code "103") (name "unconnected-(D15A-LD-Pad2)") (class "Default")
      (node (ref "D15") (pin "2") (pinfunction "LD_2") (pintype "output"))
    )
    (net (code "104") (name "unconnected-(D15A-OUT0-Pad42)") (class "Default")
      (node (ref "D15") (pin "42") (pinfunction "OUT0_42") (pintype "output"))
    )
    (net (code "105") (name "unconnected-(D15A-OUT1-Pad39)") (class "Default")
      (node (ref "D15") (pin "39") (pinfunction "OUT1_39") (pintype "output"))
    )
    (net (code "106") (name "unconnected-(D15A-OUT2-Pad19)") (class "Default")
      (node (ref "D15") (pin "19") (pinfunction "OUT2_19") (pintype "output"))
    )
    (net (code "107") (name "unconnected-(D15A-OUT3-Pad22)") (class "Default")
      (node (ref "D15") (pin "22") (pinfunction "OUT3_22") (pintype "output"))
    )
    (net (code "108") (name "unconnected-(D15A-OUT5(OUT5A)-Pad33)") (class "Default")
      (node (ref "D15") (pin "33") (pinfunction "OUT5(OUT5A)_33") (pintype "output"))
    )
    (net (code "109") (name "unconnected-(D15A-OUT6(OUT6A)-Pad26)") (class "Default")
      (node (ref "D15") (pin "26") (pinfunction "OUT6(OUT6A)_26") (pintype "output"))
    )
    (net (code "110") (name "unconnected-(D15A-OUT7(OUT7A)-Pad28)") (class "Default")
      (node (ref "D15") (pin "28") (pinfunction "OUT7(OUT7A)_28") (pintype "output"))
    )
    (net (code "111") (name "unconnected-(D15A-~{OUT0}-Pad41)") (class "Default")
      (node (ref "D15") (pin "41") (pinfunction "~{OUT0}_41") (pintype "output"))
    )
    (net (code "112") (name "unconnected-(D15A-~{OUT1}-Pad38)") (class "Default")
      (node (ref "D15") (pin "38") (pinfunction "~{OUT1}_38") (pintype "output"))
    )
    (net (code "113") (name "unconnected-(D15A-~{OUT2}-Pad20)") (class "Default")
      (node (ref "D15") (pin "20") (pinfunction "~{OUT2}_20") (pintype "output"))
    )
    (net (code "114") (name "unconnected-(D15A-~{OUT3}-Pad23)") (class "Default")
      (node (ref "D15") (pin "23") (pinfunction "~{OUT3}_23") (pintype "output"))
    )
    (net (code "115") (name "unconnected-(D15A-~{OUT5}(OUT5B)-Pad32)") (class "Default")
      (node (ref "D15") (pin "32") (pinfunction "~{OUT5}(OUT5B)_32") (pintype "output"))
    )
    (net (code "116") (name "unconnected-(D15A-~{OUT6}(OUT6B)-Pad27)") (class "Default")
      (node (ref "D15") (pin "27") (pinfunction "~{OUT6}(OUT6B)_27") (pintype "output"))
    )
    (net (code "117") (name "unconnected-(D15A-~{OUT7}(OUT7B)-Pad29)") (class "Default")
      (node (ref "D15") (pin "29") (pinfunction "~{OUT7}(OUT7B)_29") (pintype "output"))
    )
    (net (code "118") (name "unconnected-(D15A-~{PD}-Pad18)") (class "Default")
      (node (ref "D15") (pin "18") (pinfunction "~{PD}_18") (pintype "input"))
    )
    (net (code "119") (name "unconnected-(D15A-~{RESET}-Pad17)") (class "Default")
      (node (ref "D15") (pin "17") (pinfunction "~{RESET}_17") (pintype "input"))
    )
    (net (code "120") (name "unconnected-(D15A-~{SYNC}-Pad7)") (class "Default")
      (node (ref "D15") (pin "7") (pinfunction "~{SYNC}_7") (pintype "input"))
    )
    (net (code "121") (name "unconnected-(T1-Pad5)") (class "Default")
      (node (ref "T1") (pin "5") (pinfunction "5_5") (pintype "passive"))
    )
    (net (code "122") (name "unconnected-(T2-Pad5)") (class "Default")
      (node (ref "T2") (pin "5") (pinfunction "5_5") (pintype "passive"))
    )
  )
)
